# data_left.net
KiCad netlist of a schematic drawn in Altium Designer
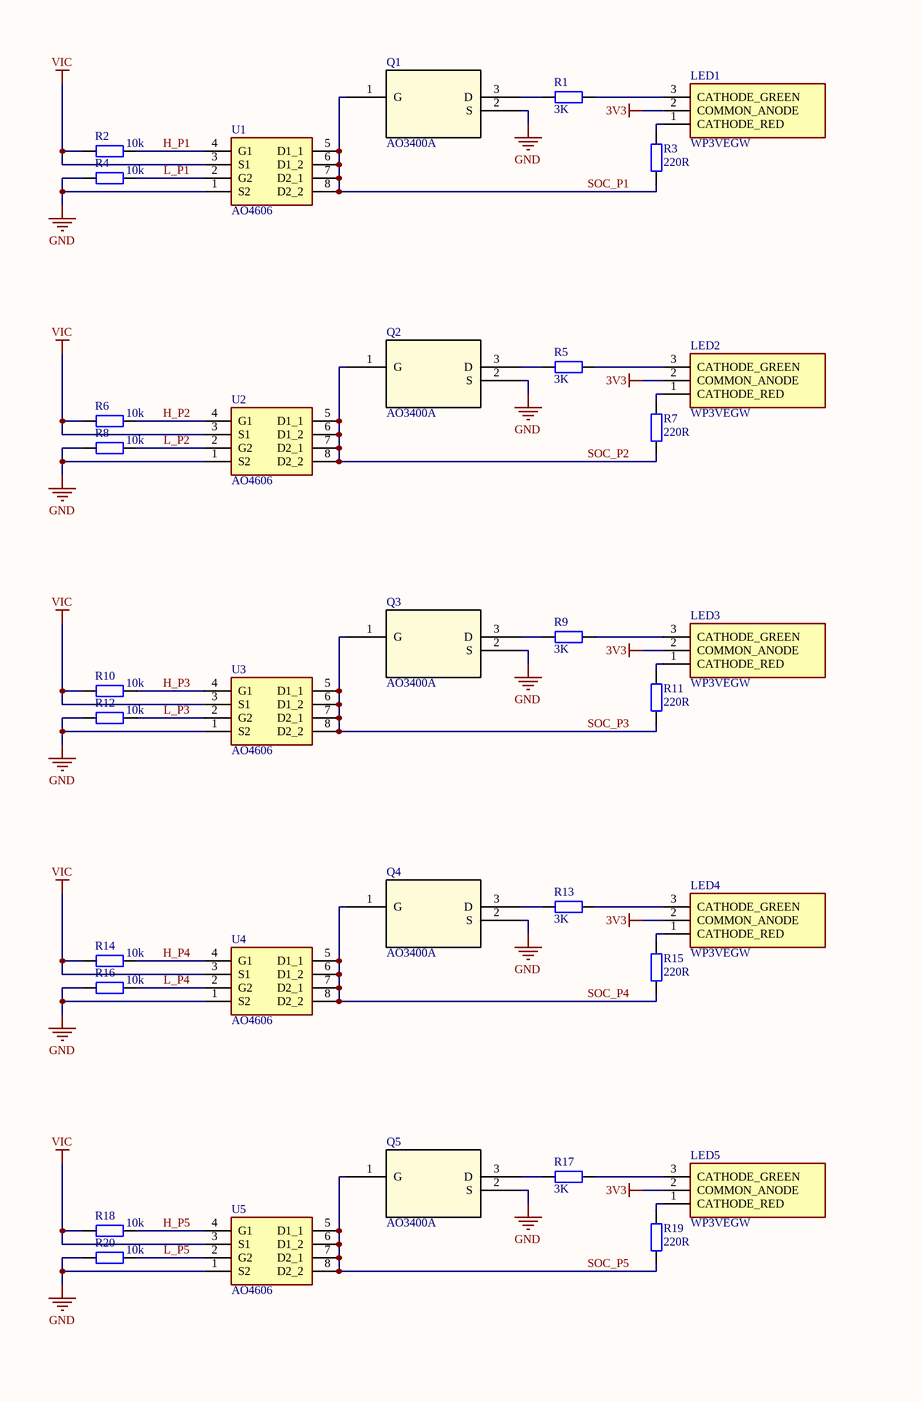
[diagram p0: data_left.SchDoc, top]
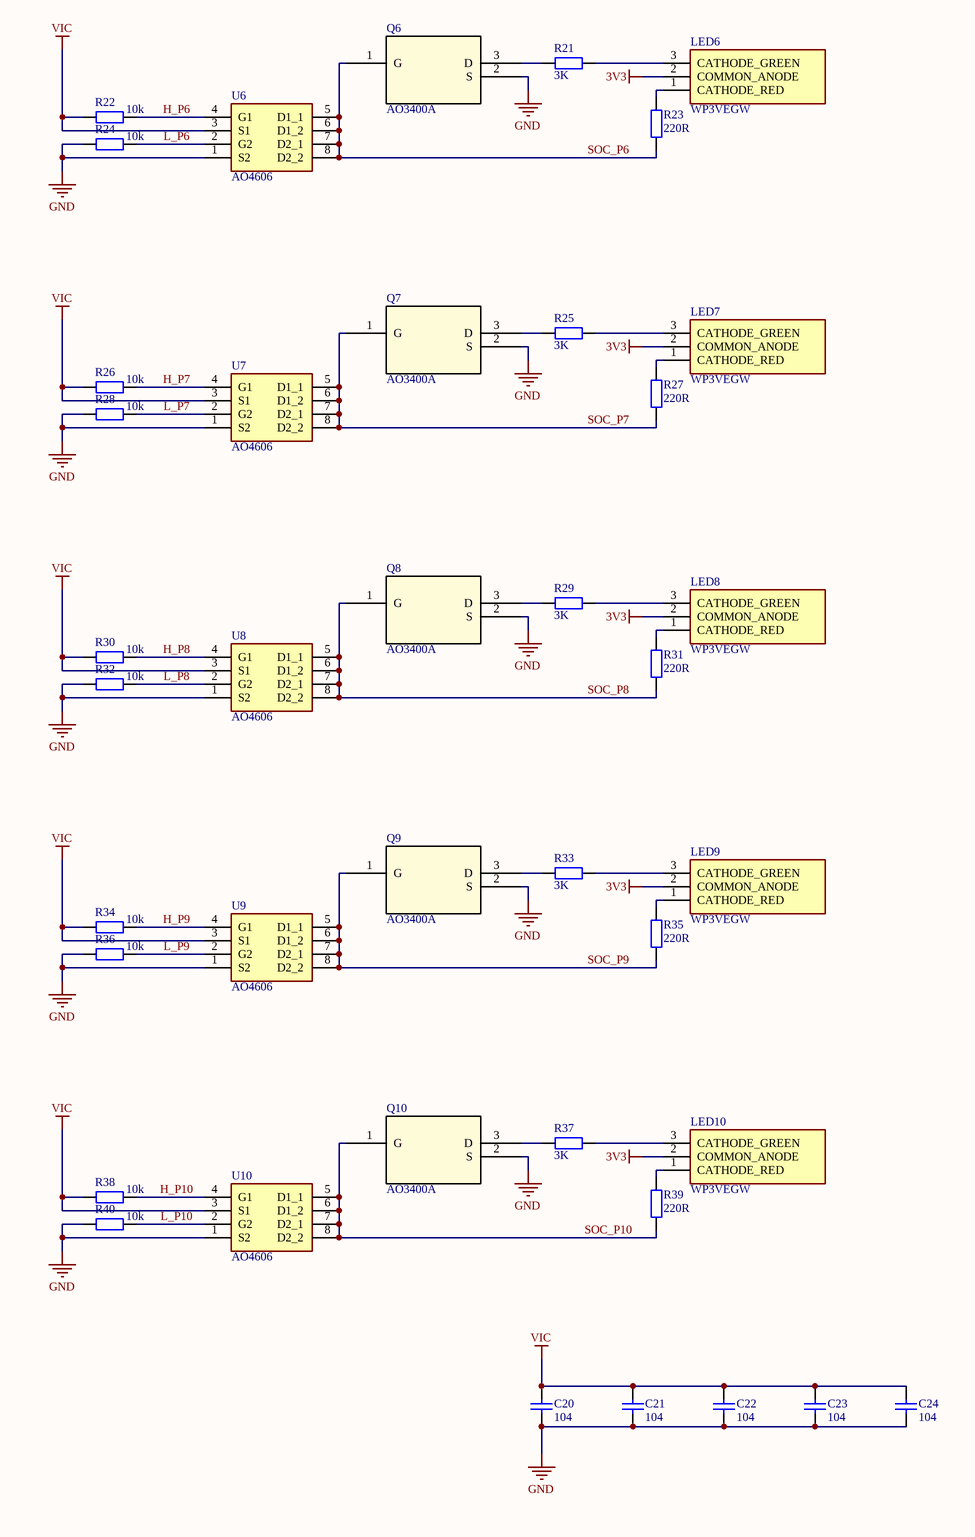
[diagram p1: data_left.SchDoc, bottom]

(export (version "E")
  (design (tool "Eeschema 10.0.6"))
  (components
    (comp (ref "C20")
      (value "104")
      (footprint "tu 0805")
      (description "Dán")
      (libsource (lib "thuvien") (part "Tu 0805 106 16V 10%"))
    )
    (comp (ref "C21")
      (value "104")
      (footprint "tu 0805")
      (description "Dán")
      (libsource (lib "thuvien") (part "Tu 0805 106 16V 10%"))
    )
    (comp (ref "C22")
      (value "104")
      (footprint "tu 0805")
      (description "Dán")
      (libsource (lib "thuvien") (part "Tu 0805 106 16V 10%"))
    )
    (comp (ref "C23")
      (value "104")
      (footprint "tu 0805")
      (description "Dán")
      (libsource (lib "thuvien") (part "Tu 0805 106 16V 10%"))
    )
    (comp (ref "C24")
      (value "104")
      (footprint "tu 0805")
      (description "Dán")
      (libsource (lib "thuvien") (part "Tu 0805 106 16V 10%"))
    )
    (comp (ref "LED1")
      (value "WP3VEGW")
      (footprint "WP3VEGW")
      (description "LED RED/GREEN 3mm")
      (fields (field (name "MOUSER PART NUMBER") "604-WP3VEGW"))
      (libsource (lib "thuvien") (part "WP3VEGW"))
    )
    (comp (ref "LED2")
      (value "WP3VEGW")
      (footprint "WP3VEGW")
      (description "LED RED/GREEN 3mm")
      (fields (field (name "MOUSER PART NUMBER") "604-WP3VEGW"))
      (libsource (lib "thuvien") (part "WP3VEGW"))
    )
    (comp (ref "LED3")
      (value "WP3VEGW")
      (footprint "WP3VEGW")
      (description "LED RED/GREEN 3mm")
      (fields (field (name "MOUSER PART NUMBER") "604-WP3VEGW"))
      (libsource (lib "thuvien") (part "WP3VEGW"))
    )
    (comp (ref "LED4")
      (value "WP3VEGW")
      (footprint "WP3VEGW")
      (description "LED RED/GREEN 3mm")
      (fields (field (name "MOUSER PART NUMBER") "604-WP3VEGW"))
      (libsource (lib "thuvien") (part "WP3VEGW"))
    )
    (comp (ref "LED5")
      (value "WP3VEGW")
      (footprint "WP3VEGW")
      (description "LED RED/GREEN 3mm")
      (fields (field (name "MOUSER PART NUMBER") "604-WP3VEGW"))
      (libsource (lib "thuvien") (part "WP3VEGW"))
    )
    (comp (ref "LED6")
      (value "WP3VEGW")
      (footprint "WP3VEGW")
      (description "LED RED/GREEN 3mm")
      (fields (field (name "MOUSER PART NUMBER") "604-WP3VEGW"))
      (libsource (lib "thuvien") (part "WP3VEGW"))
    )
    (comp (ref "LED7")
      (value "WP3VEGW")
      (footprint "WP3VEGW")
      (description "LED RED/GREEN 3mm")
      (fields (field (name "MOUSER PART NUMBER") "604-WP3VEGW"))
      (libsource (lib "thuvien") (part "WP3VEGW"))
    )
    (comp (ref "LED8")
      (value "WP3VEGW")
      (footprint "WP3VEGW")
      (description "LED RED/GREEN 3mm")
      (fields (field (name "MOUSER PART NUMBER") "604-WP3VEGW"))
      (libsource (lib "thuvien") (part "WP3VEGW"))
    )
    (comp (ref "LED9")
      (value "WP3VEGW")
      (footprint "WP3VEGW")
      (description "LED RED/GREEN 3mm")
      (fields (field (name "MOUSER PART NUMBER") "604-WP3VEGW"))
      (libsource (lib "thuvien") (part "WP3VEGW"))
    )
    (comp (ref "LED10")
      (value "WP3VEGW")
      (footprint "WP3VEGW")
      (description "LED RED/GREEN 3mm")
      (fields (field (name "MOUSER PART NUMBER") "604-WP3VEGW"))
      (libsource (lib "thuvien") (part "WP3VEGW"))
    )
    (comp (ref "Q1")
      (value "AO3400A")
      (footprint "SOT-23-3L_AOS")
      (description "N-MOSFET")
      (fields (field (name "COPYRIGHT") "Copyright (C) 2023 Ultra Librarian. All rights reserved."))
      (libsource (lib "thuvien") (part "AO3400A"))
    )
    (comp (ref "Q2")
      (value "AO3400A")
      (footprint "SOT-23-3L_AOS")
      (description "N-MOSFET")
      (fields (field (name "COPYRIGHT") "Copyright (C) 2023 Ultra Librarian. All rights reserved."))
      (libsource (lib "thuvien") (part "AO3400A"))
    )
    (comp (ref "Q3")
      (value "AO3400A")
      (footprint "SOT-23-3L_AOS")
      (description "N-MOSFET")
      (fields (field (name "COPYRIGHT") "Copyright (C) 2023 Ultra Librarian. All rights reserved."))
      (libsource (lib "thuvien") (part "AO3400A"))
    )
    (comp (ref "Q4")
      (value "AO3400A")
      (footprint "SOT-23-3L_AOS")
      (description "N-MOSFET")
      (fields (field (name "COPYRIGHT") "Copyright (C) 2023 Ultra Librarian. All rights reserved."))
      (libsource (lib "thuvien") (part "AO3400A"))
    )
    (comp (ref "Q5")
      (value "AO3400A")
      (footprint "SOT-23-3L_AOS")
      (description "N-MOSFET")
      (fields (field (name "COPYRIGHT") "Copyright (C) 2023 Ultra Librarian. All rights reserved."))
      (libsource (lib "thuvien") (part "AO3400A"))
    )
    (comp (ref "Q6")
      (value "AO3400A")
      (footprint "SOT-23-3L_AOS")
      (description "N-MOSFET")
      (fields (field (name "COPYRIGHT") "Copyright (C) 2023 Ultra Librarian. All rights reserved."))
      (libsource (lib "thuvien") (part "AO3400A"))
    )
    (comp (ref "Q7")
      (value "AO3400A")
      (footprint "SOT-23-3L_AOS")
      (description "N-MOSFET")
      (fields (field (name "COPYRIGHT") "Copyright (C) 2023 Ultra Librarian. All rights reserved."))
      (libsource (lib "thuvien") (part "AO3400A"))
    )
    (comp (ref "Q8")
      (value "AO3400A")
      (footprint "SOT-23-3L_AOS")
      (description "N-MOSFET")
      (fields (field (name "COPYRIGHT") "Copyright (C) 2023 Ultra Librarian. All rights reserved."))
      (libsource (lib "thuvien") (part "AO3400A"))
    )
    (comp (ref "Q9")
      (value "AO3400A")
      (footprint "SOT-23-3L_AOS")
      (description "N-MOSFET")
      (fields (field (name "COPYRIGHT") "Copyright (C) 2023 Ultra Librarian. All rights reserved."))
      (libsource (lib "thuvien") (part "AO3400A"))
    )
    (comp (ref "Q10")
      (value "AO3400A")
      (footprint "SOT-23-3L_AOS")
      (description "N-MOSFET")
      (fields (field (name "COPYRIGHT") "Copyright (C) 2023 Ultra Librarian. All rights reserved."))
      (libsource (lib "thuvien") (part "AO3400A"))
    )
    (comp (ref "R1")
      (value "3K")
      (footprint "tro smd 0805")
      (description "Dán")
      (libsource (lib "thuvien") (part "Tro 0805 1% 10k"))
    )
    (comp (ref "R2")
      (value "10k")
      (footprint "tro smd 0805")
      (description "Dán")
      (libsource (lib "thuvien") (part "Tro 0805 1% 10k"))
    )
    (comp (ref "R3")
      (value "220R")
      (footprint "tro smd 0805")
      (description "Dán")
      (libsource (lib "thuvien") (part "Tro 0805 1% 10k"))
    )
    (comp (ref "R4")
      (value "10k")
      (footprint "tro smd 0805")
      (description "Dán")
      (libsource (lib "thuvien") (part "Tro 0805 1% 10k"))
    )
    (comp (ref "R5")
      (value "3K")
      (footprint "tro smd 0805")
      (description "Dán")
      (libsource (lib "thuvien") (part "Tro 0805 1% 10k"))
    )
    (comp (ref "R6")
      (value "10k")
      (footprint "tro smd 0805")
      (description "Dán")
      (libsource (lib "thuvien") (part "Tro 0805 1% 10k"))
    )
    (comp (ref "R7")
      (value "220R")
      (footprint "tro smd 0805")
      (description "Dán")
      (libsource (lib "thuvien") (part "Tro 0805 1% 10k"))
    )
    (comp (ref "R8")
      (value "10k")
      (footprint "tro smd 0805")
      (description "Dán")
      (libsource (lib "thuvien") (part "Tro 0805 1% 10k"))
    )
    (comp (ref "R9")
      (value "3K")
      (footprint "tro smd 0805")
      (description "Dán")
      (libsource (lib "thuvien") (part "Tro 0805 1% 10k"))
    )
    (comp (ref "R10")
      (value "10k")
      (footprint "tro smd 0805")
      (description "Dán")
      (libsource (lib "thuvien") (part "Tro 0805 1% 10k"))
    )
    (comp (ref "R11")
      (value "220R")
      (footprint "tro smd 0805")
      (description "Dán")
      (libsource (lib "thuvien") (part "Tro 0805 1% 10k"))
    )
    (comp (ref "R12")
      (value "10k")
      (footprint "tro smd 0805")
      (description "Dán")
      (libsource (lib "thuvien") (part "Tro 0805 1% 10k"))
    )
    (comp (ref "R13")
      (value "3K")
      (footprint "tro smd 0805")
      (description "Dán")
      (libsource (lib "thuvien") (part "Tro 0805 1% 10k"))
    )
    (comp (ref "R14")
      (value "10k")
      (footprint "tro smd 0805")
      (description "Dán")
      (libsource (lib "thuvien") (part "Tro 0805 1% 10k"))
    )
    (comp (ref "R15")
      (value "220R")
      (footprint "tro smd 0805")
      (description "Dán")
      (libsource (lib "thuvien") (part "Tro 0805 1% 10k"))
    )
    (comp (ref "R16")
      (value "10k")
      (footprint "tro smd 0805")
      (description "Dán")
      (libsource (lib "thuvien") (part "Tro 0805 1% 10k"))
    )
    (comp (ref "R17")
      (value "3K")
      (footprint "tro smd 0805")
      (description "Dán")
      (libsource (lib "thuvien") (part "Tro 0805 1% 10k"))
    )
    (comp (ref "R18")
      (value "10k")
      (footprint "tro smd 0805")
      (description "Dán")
      (libsource (lib "thuvien") (part "Tro 0805 1% 10k"))
    )
    (comp (ref "R19")
      (value "220R")
      (footprint "tro smd 0805")
      (description "Dán")
      (libsource (lib "thuvien") (part "Tro 0805 1% 10k"))
    )
    (comp (ref "R20")
      (value "10k")
      (footprint "tro smd 0805")
      (description "Dán")
      (libsource (lib "thuvien") (part "Tro 0805 1% 10k"))
    )
    (comp (ref "R21")
      (value "3K")
      (footprint "tro smd 0805")
      (description "Dán")
      (libsource (lib "thuvien") (part "Tro 0805 1% 10k"))
    )
    (comp (ref "R22")
      (value "10k")
      (footprint "tro smd 0805")
      (description "Dán")
      (libsource (lib "thuvien") (part "Tro 0805 1% 10k"))
    )
    (comp (ref "R23")
      (value "220R")
      (footprint "tro smd 0805")
      (description "Dán")
      (libsource (lib "thuvien") (part "Tro 0805 1% 10k"))
    )
    (comp (ref "R24")
      (value "10k")
      (footprint "tro smd 0805")
      (description "Dán")
      (libsource (lib "thuvien") (part "Tro 0805 1% 10k"))
    )
    (comp (ref "R25")
      (value "3K")
      (footprint "tro smd 0805")
      (description "Dán")
      (libsource (lib "thuvien") (part "Tro 0805 1% 10k"))
    )
    (comp (ref "R26")
      (value "10k")
      (footprint "tro smd 0805")
      (description "Dán")
      (libsource (lib "thuvien") (part "Tro 0805 1% 10k"))
    )
    (comp (ref "R27")
      (value "220R")
      (footprint "tro smd 0805")
      (description "Dán")
      (libsource (lib "thuvien") (part "Tro 0805 1% 10k"))
    )
    (comp (ref "R28")
      (value "10k")
      (footprint "tro smd 0805")
      (description "Dán")
      (libsource (lib "thuvien") (part "Tro 0805 1% 10k"))
    )
    (comp (ref "R29")
      (value "3K")
      (footprint "tro smd 0805")
      (description "Dán")
      (libsource (lib "thuvien") (part "Tro 0805 1% 10k"))
    )
    (comp (ref "R30")
      (value "10k")
      (footprint "tro smd 0805")
      (description "Dán")
      (libsource (lib "thuvien") (part "Tro 0805 1% 10k"))
    )
    (comp (ref "R31")
      (value "220R")
      (footprint "tro smd 0805")
      (description "Dán")
      (libsource (lib "thuvien") (part "Tro 0805 1% 10k"))
    )
    (comp (ref "R32")
      (value "10k")
      (footprint "tro smd 0805")
      (description "Dán")
      (libsource (lib "thuvien") (part "Tro 0805 1% 10k"))
    )
    (comp (ref "R33")
      (value "3K")
      (footprint "tro smd 0805")
      (description "Dán")
      (libsource (lib "thuvien") (part "Tro 0805 1% 10k"))
    )
    (comp (ref "R34")
      (value "10k")
      (footprint "tro smd 0805")
      (description "Dán")
      (libsource (lib "thuvien") (part "Tro 0805 1% 10k"))
    )
    (comp (ref "R35")
      (value "220R")
      (footprint "tro smd 0805")
      (description "Dán")
      (libsource (lib "thuvien") (part "Tro 0805 1% 10k"))
    )
    (comp (ref "R36")
      (value "10k")
      (footprint "tro smd 0805")
      (description "Dán")
      (libsource (lib "thuvien") (part "Tro 0805 1% 10k"))
    )
    (comp (ref "R37")
      (value "3K")
      (footprint "tro smd 0805")
      (description "Dán")
      (libsource (lib "thuvien") (part "Tro 0805 1% 10k"))
    )
    (comp (ref "R38")
      (value "10k")
      (footprint "tro smd 0805")
      (description "Dán")
      (libsource (lib "thuvien") (part "Tro 0805 1% 10k"))
    )
    (comp (ref "R39")
      (value "220R")
      (footprint "tro smd 0805")
      (description "Dán")
      (libsource (lib "thuvien") (part "Tro 0805 1% 10k"))
    )
    (comp (ref "R40")
      (value "10k")
      (footprint "tro smd 0805")
      (description "Dán")
      (libsource (lib "thuvien") (part "Tro 0805 1% 10k"))
    )
    (comp (ref "U1")
      (value "AO4606")
      (footprint "SOIC127P600X175-8N")
      (libsource (lib "thuvien") (part "AO4606"))
    )
    (comp (ref "U2")
      (value "AO4606")
      (footprint "SOIC127P600X175-8N")
      (libsource (lib "thuvien") (part "AO4606"))
    )
    (comp (ref "U3")
      (value "AO4606")
      (footprint "SOIC127P600X175-8N")
      (libsource (lib "thuvien") (part "AO4606"))
    )
    (comp (ref "U4")
      (value "AO4606")
      (footprint "SOIC127P600X175-8N")
      (libsource (lib "thuvien") (part "AO4606"))
    )
    (comp (ref "U5")
      (value "AO4606")
      (footprint "SOIC127P600X175-8N")
      (libsource (lib "thuvien") (part "AO4606"))
    )
    (comp (ref "U6")
      (value "AO4606")
      (footprint "SOIC127P600X175-8N")
      (libsource (lib "thuvien") (part "AO4606"))
    )
    (comp (ref "U7")
      (value "AO4606")
      (footprint "SOIC127P600X175-8N")
      (libsource (lib "thuvien") (part "AO4606"))
    )
    (comp (ref "U8")
      (value "AO4606")
      (footprint "SOIC127P600X175-8N")
      (libsource (lib "thuvien") (part "AO4606"))
    )
    (comp (ref "U9")
      (value "AO4606")
      (footprint "SOIC127P600X175-8N")
      (libsource (lib "thuvien") (part "AO4606"))
    )
    (comp (ref "U10")
      (value "AO4606")
      (footprint "SOIC127P600X175-8N")
      (libsource (lib "thuvien") (part "AO4606"))
    )
  )
  (nets
    (net (code "1") (name "/H_P1") (class "Default")
      (node (ref "R2") (pin "2") (pinfunction "2_2") (pintype "passive"))
      (node (ref "U1") (pin "4") (pinfunction "G1_4") (pintype "passive"))
    )
    (net (code "2") (name "/H_P2") (class "Default")
      (node (ref "R6") (pin "2") (pinfunction "2_2") (pintype "passive"))
      (node (ref "U2") (pin "4") (pinfunction "G1_4") (pintype "passive"))
    )
    (net (code "3") (name "/H_P3") (class "Default")
      (node (ref "R10") (pin "2") (pinfunction "2_2") (pintype "passive"))
      (node (ref "U3") (pin "4") (pinfunction "G1_4") (pintype "passive"))
    )
    (net (code "4") (name "/H_P4") (class "Default")
      (node (ref "R14") (pin "2") (pinfunction "2_2") (pintype "passive"))
      (node (ref "U4") (pin "4") (pinfunction "G1_4") (pintype "passive"))
    )
    (net (code "5") (name "/H_P5") (class "Default")
      (node (ref "R18") (pin "2") (pinfunction "2_2") (pintype "passive"))
      (node (ref "U5") (pin "4") (pinfunction "G1_4") (pintype "passive"))
    )
    (net (code "6") (name "/H_P6") (class "Default")
      (node (ref "R22") (pin "2") (pinfunction "2_2") (pintype "passive"))
      (node (ref "U6") (pin "4") (pinfunction "G1_4") (pintype "passive"))
    )
    (net (code "7") (name "/H_P7") (class "Default")
      (node (ref "R26") (pin "2") (pinfunction "2_2") (pintype "passive"))
      (node (ref "U7") (pin "4") (pinfunction "G1_4") (pintype "passive"))
    )
    (net (code "8") (name "/H_P8") (class "Default")
      (node (ref "R30") (pin "2") (pinfunction "2_2") (pintype "passive"))
      (node (ref "U8") (pin "4") (pinfunction "G1_4") (pintype "passive"))
    )
    (net (code "9") (name "/H_P9") (class "Default")
      (node (ref "R34") (pin "2") (pinfunction "2_2") (pintype "passive"))
      (node (ref "U9") (pin "4") (pinfunction "G1_4") (pintype "passive"))
    )
    (net (code "10") (name "/H_P10") (class "Default")
      (node (ref "R38") (pin "2") (pinfunction "2_2") (pintype "passive"))
      (node (ref "U10") (pin "4") (pinfunction "G1_4") (pintype "passive"))
    )
    (net (code "11") (name "/L_P1") (class "Default")
      (node (ref "R4") (pin "2") (pinfunction "2_2") (pintype "passive"))
      (node (ref "U1") (pin "2") (pinfunction "G2_2") (pintype "passive"))
    )
    (net (code "12") (name "/L_P2") (class "Default")
      (node (ref "R8") (pin "2") (pinfunction "2_2") (pintype "passive"))
      (node (ref "U2") (pin "2") (pinfunction "G2_2") (pintype "passive"))
    )
    (net (code "13") (name "/L_P3") (class "Default")
      (node (ref "R12") (pin "2") (pinfunction "2_2") (pintype "passive"))
      (node (ref "U3") (pin "2") (pinfunction "G2_2") (pintype "passive"))
    )
    (net (code "14") (name "/L_P4") (class "Default")
      (node (ref "R16") (pin "2") (pinfunction "2_2") (pintype "passive"))
      (node (ref "U4") (pin "2") (pinfunction "G2_2") (pintype "passive"))
    )
    (net (code "15") (name "/L_P5") (class "Default")
      (node (ref "R20") (pin "2") (pinfunction "2_2") (pintype "passive"))
      (node (ref "U5") (pin "2") (pinfunction "G2_2") (pintype "passive"))
    )
    (net (code "16") (name "/L_P6") (class "Default")
      (node (ref "R24") (pin "2") (pinfunction "2_2") (pintype "passive"))
      (node (ref "U6") (pin "2") (pinfunction "G2_2") (pintype "passive"))
    )
    (net (code "17") (name "/L_P7") (class "Default")
      (node (ref "R28") (pin "2") (pinfunction "2_2") (pintype "passive"))
      (node (ref "U7") (pin "2") (pinfunction "G2_2") (pintype "passive"))
    )
    (net (code "18") (name "/L_P8") (class "Default")
      (node (ref "R32") (pin "2") (pinfunction "2_2") (pintype "passive"))
      (node (ref "U8") (pin "2") (pinfunction "G2_2") (pintype "passive"))
    )
    (net (code "19") (name "/L_P9") (class "Default")
      (node (ref "R36") (pin "2") (pinfunction "2_2") (pintype "passive"))
      (node (ref "U9") (pin "2") (pinfunction "G2_2") (pintype "passive"))
    )
    (net (code "20") (name "/L_P10") (class "Default")
      (node (ref "R40") (pin "2") (pinfunction "2_2") (pintype "passive"))
      (node (ref "U10") (pin "2") (pinfunction "G2_2") (pintype "passive"))
    )
    (net (code "21") (name "/SOC_P1") (class "Default")
      (node (ref "Q1") (pin "1") (pinfunction "G_1") (pintype "passive"))
      (node (ref "R3") (pin "1") (pinfunction "1_1") (pintype "passive"))
      (node (ref "U1") (pin "5") (pinfunction "D1_1_5") (pintype "passive"))
      (node (ref "U1") (pin "6") (pinfunction "D1_2_6") (pintype "passive"))
      (node (ref "U1") (pin "7") (pinfunction "D2_1_7") (pintype "passive"))
      (node (ref "U1") (pin "8") (pinfunction "D2_2_8") (pintype "passive"))
    )
    (net (code "22") (name "/SOC_P2") (class "Default")
      (node (ref "Q2") (pin "1") (pinfunction "G_1") (pintype "passive"))
      (node (ref "R7") (pin "1") (pinfunction "1_1") (pintype "passive"))
      (node (ref "U2") (pin "5") (pinfunction "D1_1_5") (pintype "passive"))
      (node (ref "U2") (pin "6") (pinfunction "D1_2_6") (pintype "passive"))
      (node (ref "U2") (pin "7") (pinfunction "D2_1_7") (pintype "passive"))
      (node (ref "U2") (pin "8") (pinfunction "D2_2_8") (pintype "passive"))
    )
    (net (code "23") (name "/SOC_P3") (class "Default")
      (node (ref "Q3") (pin "1") (pinfunction "G_1") (pintype "passive"))
      (node (ref "R11") (pin "1") (pinfunction "1_1") (pintype "passive"))
      (node (ref "U3") (pin "5") (pinfunction "D1_1_5") (pintype "passive"))
      (node (ref "U3") (pin "6") (pinfunction "D1_2_6") (pintype "passive"))
      (node (ref "U3") (pin "7") (pinfunction "D2_1_7") (pintype "passive"))
      (node (ref "U3") (pin "8") (pinfunction "D2_2_8") (pintype "passive"))
    )
    (net (code "24") (name "/SOC_P4") (class "Default")
      (node (ref "Q4") (pin "1") (pinfunction "G_1") (pintype "passive"))
      (node (ref "R15") (pin "1") (pinfunction "1_1") (pintype "passive"))
      (node (ref "U4") (pin "5") (pinfunction "D1_1_5") (pintype "passive"))
      (node (ref "U4") (pin "6") (pinfunction "D1_2_6") (pintype "passive"))
      (node (ref "U4") (pin "7") (pinfunction "D2_1_7") (pintype "passive"))
      (node (ref "U4") (pin "8") (pinfunction "D2_2_8") (pintype "passive"))
    )
    (net (code "25") (name "/SOC_P5") (class "Default")
      (node (ref "Q5") (pin "1") (pinfunction "G_1") (pintype "passive"))
      (node (ref "R19") (pin "1") (pinfunction "1_1") (pintype "passive"))
      (node (ref "U5") (pin "5") (pinfunction "D1_1_5") (pintype "passive"))
      (node (ref "U5") (pin "6") (pinfunction "D1_2_6") (pintype "passive"))
      (node (ref "U5") (pin "7") (pinfunction "D2_1_7") (pintype "passive"))
      (node (ref "U5") (pin "8") (pinfunction "D2_2_8") (pintype "passive"))
    )
    (net (code "26") (name "/SOC_P6") (class "Default")
      (node (ref "Q6") (pin "1") (pinfunction "G_1") (pintype "passive"))
      (node (ref "R23") (pin "1") (pinfunction "1_1") (pintype "passive"))
      (node (ref "U6") (pin "5") (pinfunction "D1_1_5") (pintype "passive"))
      (node (ref "U6") (pin "6") (pinfunction "D1_2_6") (pintype "passive"))
      (node (ref "U6") (pin "7") (pinfunction "D2_1_7") (pintype "passive"))
      (node (ref "U6") (pin "8") (pinfunction "D2_2_8") (pintype "passive"))
    )
    (net (code "27") (name "/SOC_P7") (class "Default")
      (node (ref "Q7") (pin "1") (pinfunction "G_1") (pintype "passive"))
      (node (ref "R27") (pin "1") (pinfunction "1_1") (pintype "passive"))
      (node (ref "U7") (pin "5") (pinfunction "D1_1_5") (pintype "passive"))
      (node (ref "U7") (pin "6") (pinfunction "D1_2_6") (pintype "passive"))
      (node (ref "U7") (pin "7") (pinfunction "D2_1_7") (pintype "passive"))
      (node (ref "U7") (pin "8") (pinfunction "D2_2_8") (pintype "passive"))
    )
    (net (code "28") (name "/SOC_P8") (class "Default")
      (node (ref "Q8") (pin "1") (pinfunction "G_1") (pintype "passive"))
      (node (ref "R31") (pin "1") (pinfunction "1_1") (pintype "passive"))
      (node (ref "U8") (pin "5") (pinfunction "D1_1_5") (pintype "passive"))
      (node (ref "U8") (pin "6") (pinfunction "D1_2_6") (pintype "passive"))
      (node (ref "U8") (pin "7") (pinfunction "D2_1_7") (pintype "passive"))
      (node (ref "U8") (pin "8") (pinfunction "D2_2_8") (pintype "passive"))
    )
    (net (code "29") (name "/SOC_P9") (class "Default")
      (node (ref "Q9") (pin "1") (pinfunction "G_1") (pintype "passive"))
      (node (ref "R35") (pin "1") (pinfunction "1_1") (pintype "passive"))
      (node (ref "U9") (pin "5") (pinfunction "D1_1_5") (pintype "passive"))
      (node (ref "U9") (pin "6") (pinfunction "D1_2_6") (pintype "passive"))
      (node (ref "U9") (pin "7") (pinfunction "D2_1_7") (pintype "passive"))
      (node (ref "U9") (pin "8") (pinfunction "D2_2_8") (pintype "passive"))
    )
    (net (code "30") (name "/SOC_P10") (class "Default")
      (node (ref "Q10") (pin "1") (pinfunction "G_1") (pintype "passive"))
      (node (ref "R39") (pin "1") (pinfunction "1_1") (pintype "passive"))
      (node (ref "U10") (pin "5") (pinfunction "D1_1_5") (pintype "passive"))
      (node (ref "U10") (pin "6") (pinfunction "D1_2_6") (pintype "passive"))
      (node (ref "U10") (pin "7") (pinfunction "D2_1_7") (pintype "passive"))
      (node (ref "U10") (pin "8") (pinfunction "D2_2_8") (pintype "passive"))
    )
    (net (code "31") (name "3V3") (class "Default")
      (node (ref "LED1") (pin "2") (pinfunction "COMMON_ANODE_2") (pintype "passive"))
      (node (ref "LED10") (pin "2") (pinfunction "COMMON_ANODE_2") (pintype "passive"))
      (node (ref "LED2") (pin "2") (pinfunction "COMMON_ANODE_2") (pintype "passive"))
      (node (ref "LED3") (pin "2") (pinfunction "COMMON_ANODE_2") (pintype "passive"))
      (node (ref "LED4") (pin "2") (pinfunction "COMMON_ANODE_2") (pintype "passive"))
      (node (ref "LED5") (pin "2") (pinfunction "COMMON_ANODE_2") (pintype "passive"))
      (node (ref "LED6") (pin "2") (pinfunction "COMMON_ANODE_2") (pintype "passive"))
      (node (ref "LED7") (pin "2") (pinfunction "COMMON_ANODE_2") (pintype "passive"))
      (node (ref "LED8") (pin "2") (pinfunction "COMMON_ANODE_2") (pintype "passive"))
      (node (ref "LED9") (pin "2") (pinfunction "COMMON_ANODE_2") (pintype "passive"))
    )
    (net (code "32") (name "GND") (class "Default")
      (node (ref "C20") (pin "2") (pinfunction "2_2") (pintype "passive"))
      (node (ref "C21") (pin "2") (pinfunction "2_2") (pintype "passive"))
      (node (ref "C22") (pin "2") (pinfunction "2_2") (pintype "passive"))
      (node (ref "C23") (pin "2") (pinfunction "2_2") (pintype "passive"))
      (node (ref "C24") (pin "2") (pinfunction "2_2") (pintype "passive"))
      (node (ref "Q1") (pin "2") (pinfunction "S_2") (pintype "passive"))
      (node (ref "Q10") (pin "2") (pinfunction "S_2") (pintype "passive"))
      (node (ref "Q2") (pin "2") (pinfunction "S_2") (pintype "passive"))
      (node (ref "Q3") (pin "2") (pinfunction "S_2") (pintype "passive"))
      (node (ref "Q4") (pin "2") (pinfunction "S_2") (pintype "passive"))
      (node (ref "Q5") (pin "2") (pinfunction "S_2") (pintype "passive"))
      (node (ref "Q6") (pin "2") (pinfunction "S_2") (pintype "passive"))
      (node (ref "Q7") (pin "2") (pinfunction "S_2") (pintype "passive"))
      (node (ref "Q8") (pin "2") (pinfunction "S_2") (pintype "passive"))
      (node (ref "Q9") (pin "2") (pinfunction "S_2") (pintype "passive"))
      (node (ref "R12") (pin "1") (pinfunction "1_1") (pintype "passive"))
      (node (ref "R16") (pin "1") (pinfunction "1_1") (pintype "passive"))
      (node (ref "R20") (pin "1") (pinfunction "1_1") (pintype "passive"))
      (node (ref "R24") (pin "1") (pinfunction "1_1") (pintype "passive"))
      (node (ref "R28") (pin "1") (pinfunction "1_1") (pintype "passive"))
      (node (ref "R32") (pin "1") (pinfunction "1_1") (pintype "passive"))
      (node (ref "R36") (pin "1") (pinfunction "1_1") (pintype "passive"))
      (node (ref "R4") (pin "1") (pinfunction "1_1") (pintype "passive"))
      (node (ref "R40") (pin "1") (pinfunction "1_1") (pintype "passive"))
      (node (ref "R8") (pin "1") (pinfunction "1_1") (pintype "passive"))
      (node (ref "U1") (pin "1") (pinfunction "S2_1") (pintype "passive"))
      (node (ref "U10") (pin "1") (pinfunction "S2_1") (pintype "passive"))
      (node (ref "U2") (pin "1") (pinfunction "S2_1") (pintype "passive"))
      (node (ref "U3") (pin "1") (pinfunction "S2_1") (pintype "passive"))
      (node (ref "U4") (pin "1") (pinfunction "S2_1") (pintype "passive"))
      (node (ref "U5") (pin "1") (pinfunction "S2_1") (pintype "passive"))
      (node (ref "U6") (pin "1") (pinfunction "S2_1") (pintype "passive"))
      (node (ref "U7") (pin "1") (pinfunction "S2_1") (pintype "passive"))
      (node (ref "U8") (pin "1") (pinfunction "S2_1") (pintype "passive"))
      (node (ref "U9") (pin "1") (pinfunction "S2_1") (pintype "passive"))
    )
    (net (code "33") (name "Net-(LED1-CATHODE_GREEN)") (class "Default")
      (node (ref "LED1") (pin "3") (pinfunction "CATHODE_GREEN_3") (pintype "passive"))
      (node (ref "R1") (pin "1") (pinfunction "1_1") (pintype "passive"))
    )
    (net (code "34") (name "Net-(LED1-CATHODE_RED)") (class "Default")
      (node (ref "LED1") (pin "1") (pinfunction "CATHODE_RED_1") (pintype "passive"))
      (node (ref "R3") (pin "2") (pinfunction "2_2") (pintype "passive"))
    )
    (net (code "35") (name "Net-(LED2-CATHODE_GREEN)") (class "Default")
      (node (ref "LED2") (pin "3") (pinfunction "CATHODE_GREEN_3") (pintype "passive"))
      (node (ref "R5") (pin "1") (pinfunction "1_1") (pintype "passive"))
    )
    (net (code "36") (name "Net-(LED2-CATHODE_RED)") (class "Default")
      (node (ref "LED2") (pin "1") (pinfunction "CATHODE_RED_1") (pintype "passive"))
      (node (ref "R7") (pin "2") (pinfunction "2_2") (pintype "passive"))
    )
    (net (code "37") (name "Net-(LED3-CATHODE_GREEN)") (class "Default")
      (node (ref "LED3") (pin "3") (pinfunction "CATHODE_GREEN_3") (pintype "passive"))
      (node (ref "R9") (pin "1") (pinfunction "1_1") (pintype "passive"))
    )
    (net (code "38") (name "Net-(LED3-CATHODE_RED)") (class "Default")
      (node (ref "LED3") (pin "1") (pinfunction "CATHODE_RED_1") (pintype "passive"))
      (node (ref "R11") (pin "2") (pinfunction "2_2") (pintype "passive"))
    )
    (net (code "39") (name "Net-(LED4-CATHODE_GREEN)") (class "Default")
      (node (ref "LED4") (pin "3") (pinfunction "CATHODE_GREEN_3") (pintype "passive"))
      (node (ref "R13") (pin "1") (pinfunction "1_1") (pintype "passive"))
    )
    (net (code "40") (name "Net-(LED4-CATHODE_RED)") (class "Default")
      (node (ref "LED4") (pin "1") (pinfunction "CATHODE_RED_1") (pintype "passive"))
      (node (ref "R15") (pin "2") (pinfunction "2_2") (pintype "passive"))
    )
    (net (code "41") (name "Net-(LED5-CATHODE_GREEN)") (class "Default")
      (node (ref "LED5") (pin "3") (pinfunction "CATHODE_GREEN_3") (pintype "passive"))
      (node (ref "R17") (pin "1") (pinfunction "1_1") (pintype "passive"))
    )
    (net (code "42") (name "Net-(LED5-CATHODE_RED)") (class "Default")
      (node (ref "LED5") (pin "1") (pinfunction "CATHODE_RED_1") (pintype "passive"))
      (node (ref "R19") (pin "2") (pinfunction "2_2") (pintype "passive"))
    )
    (net (code "43") (name "Net-(LED6-CATHODE_GREEN)") (class "Default")
      (node (ref "LED6") (pin "3") (pinfunction "CATHODE_GREEN_3") (pintype "passive"))
      (node (ref "R21") (pin "1") (pinfunction "1_1") (pintype "passive"))
    )
    (net (code "44") (name "Net-(LED6-CATHODE_RED)") (class "Default")
      (node (ref "LED6") (pin "1") (pinfunction "CATHODE_RED_1") (pintype "passive"))
      (node (ref "R23") (pin "2") (pinfunction "2_2") (pintype "passive"))
    )
    (net (code "45") (name "Net-(LED7-CATHODE_GREEN)") (class "Default")
      (node (ref "LED7") (pin "3") (pinfunction "CATHODE_GREEN_3") (pintype "passive"))
      (node (ref "R25") (pin "1") (pinfunction "1_1") (pintype "passive"))
    )
    (net (code "46") (name "Net-(LED7-CATHODE_RED)") (class "Default")
      (node (ref "LED7") (pin "1") (pinfunction "CATHODE_RED_1") (pintype "passive"))
      (node (ref "R27") (pin "2") (pinfunction "2_2") (pintype "passive"))
    )
    (net (code "47") (name "Net-(LED8-CATHODE_GREEN)") (class "Default")
      (node (ref "LED8") (pin "3") (pinfunction "CATHODE_GREEN_3") (pintype "passive"))
      (node (ref "R29") (pin "1") (pinfunction "1_1") (pintype "passive"))
    )
    (net (code "48") (name "Net-(LED8-CATHODE_RED)") (class "Default")
      (node (ref "LED8") (pin "1") (pinfunction "CATHODE_RED_1") (pintype "passive"))
      (node (ref "R31") (pin "2") (pinfunction "2_2") (pintype "passive"))
    )
    (net (code "49") (name "Net-(LED9-CATHODE_GREEN)") (class "Default")
      (node (ref "LED9") (pin "3") (pinfunction "CATHODE_GREEN_3") (pintype "passive"))
      (node (ref "R33") (pin "1") (pinfunction "1_1") (pintype "passive"))
    )
    (net (code "50") (name "Net-(LED9-CATHODE_RED)") (class "Default")
      (node (ref "LED9") (pin "1") (pinfunction "CATHODE_RED_1") (pintype "passive"))
      (node (ref "R35") (pin "2") (pinfunction "2_2") (pintype "passive"))
    )
    (net (code "51") (name "Net-(LED10-CATHODE_GREEN)") (class "Default")
      (node (ref "LED10") (pin "3") (pinfunction "CATHODE_GREEN_3") (pintype "passive"))
      (node (ref "R37") (pin "1") (pinfunction "1_1") (pintype "passive"))
    )
    (net (code "52") (name "Net-(LED10-CATHODE_RED)") (class "Default")
      (node (ref "LED10") (pin "1") (pinfunction "CATHODE_RED_1") (pintype "passive"))
      (node (ref "R39") (pin "2") (pinfunction "2_2") (pintype "passive"))
    )
    (net (code "53") (name "Net-(Q1-D)") (class "Default")
      (node (ref "Q1") (pin "3") (pinfunction "D_3") (pintype "passive"))
      (node (ref "R1") (pin "2") (pinfunction "2_2") (pintype "passive"))
    )
    (net (code "54") (name "Net-(Q2-D)") (class "Default")
      (node (ref "Q2") (pin "3") (pinfunction "D_3") (pintype "passive"))
      (node (ref "R5") (pin "2") (pinfunction "2_2") (pintype "passive"))
    )
    (net (code "55") (name "Net-(Q3-D)") (class "Default")
      (node (ref "Q3") (pin "3") (pinfunction "D_3") (pintype "passive"))
      (node (ref "R9") (pin "2") (pinfunction "2_2") (pintype "passive"))
    )
    (net (code "56") (name "Net-(Q4-D)") (class "Default")
      (node (ref "Q4") (pin "3") (pinfunction "D_3") (pintype "passive"))
      (node (ref "R13") (pin "2") (pinfunction "2_2") (pintype "passive"))
    )
    (net (code "57") (name "Net-(Q5-D)") (class "Default")
      (node (ref "Q5") (pin "3") (pinfunction "D_3") (pintype "passive"))
      (node (ref "R17") (pin "2") (pinfunction "2_2") (pintype "passive"))
    )
    (net (code "58") (name "Net-(Q6-D)") (class "Default")
      (node (ref "Q6") (pin "3") (pinfunction "D_3") (pintype "passive"))
      (node (ref "R21") (pin "2") (pinfunction "2_2") (pintype "passive"))
    )
    (net (code "59") (name "Net-(Q7-D)") (class "Default")
      (node (ref "Q7") (pin "3") (pinfunction "D_3") (pintype "passive"))
      (node (ref "R25") (pin "2") (pinfunction "2_2") (pintype "passive"))
    )
    (net (code "60") (name "Net-(Q8-D)") (class "Default")
      (node (ref "Q8") (pin "3") (pinfunction "D_3") (pintype "passive"))
      (node (ref "R29") (pin "2") (pinfunction "2_2") (pintype "passive"))
    )
    (net (code "61") (name "Net-(Q9-D)") (class "Default")
      (node (ref "Q9") (pin "3") (pinfunction "D_3") (pintype "passive"))
      (node (ref "R33") (pin "2") (pinfunction "2_2") (pintype "passive"))
    )
    (net (code "62") (name "Net-(Q10-D)") (class "Default")
      (node (ref "Q10") (pin "3") (pinfunction "D_3") (pintype "passive"))
      (node (ref "R37") (pin "2") (pinfunction "2_2") (pintype "passive"))
    )
    (net (code "63") (name "VIC") (class "Default")
      (node (ref "C20") (pin "1") (pinfunction "1_1") (pintype "passive"))
      (node (ref "C21") (pin "1") (pinfunction "1_1") (pintype "passive"))
      (node (ref "C22") (pin "1") (pinfunction "1_1") (pintype "passive"))
      (node (ref "C23") (pin "1") (pinfunction "1_1") (pintype "passive"))
      (node (ref "C24") (pin "1") (pinfunction "1_1") (pintype "passive"))
      (node (ref "R10") (pin "1") (pinfunction "1_1") (pintype "passive"))
      (node (ref "R14") (pin "1") (pinfunction "1_1") (pintype "passive"))
      (node (ref "R18") (pin "1") (pinfunction "1_1") (pintype "passive"))
      (node (ref "R2") (pin "1") (pinfunction "1_1") (pintype "passive"))
      (node (ref "R22") (pin "1") (pinfunction "1_1") (pintype "passive"))
      (node (ref "R26") (pin "1") (pinfunction "1_1") (pintype "passive"))
      (node (ref "R30") (pin "1") (pinfunction "1_1") (pintype "passive"))
      (node (ref "R34") (pin "1") (pinfunction "1_1") (pintype "passive"))
      (node (ref "R38") (pin "1") (pinfunction "1_1") (pintype "passive"))
      (node (ref "R6") (pin "1") (pinfunction "1_1") (pintype "passive"))
      (node (ref "U1") (pin "3") (pinfunction "S1_3") (pintype "passive"))
      (node (ref "U10") (pin "3") (pinfunction "S1_3") (pintype "passive"))
      (node (ref "U2") (pin "3") (pinfunction "S1_3") (pintype "passive"))
      (node (ref "U3") (pin "3") (pinfunction "S1_3") (pintype "passive"))
      (node (ref "U4") (pin "3") (pinfunction "S1_3") (pintype "passive"))
      (node (ref "U5") (pin "3") (pinfunction "S1_3") (pintype "passive"))
      (node (ref "U6") (pin "3") (pinfunction "S1_3") (pintype "passive"))
      (node (ref "U7") (pin "3") (pinfunction "S1_3") (pintype "passive"))
      (node (ref "U8") (pin "3") (pinfunction "S1_3") (pintype "passive"))
      (node (ref "U9") (pin "3") (pinfunction "S1_3") (pintype "passive"))
    )
  )
)
